# respirho2pile.net
KiCad netlist of a schematic drawn in EAGLE
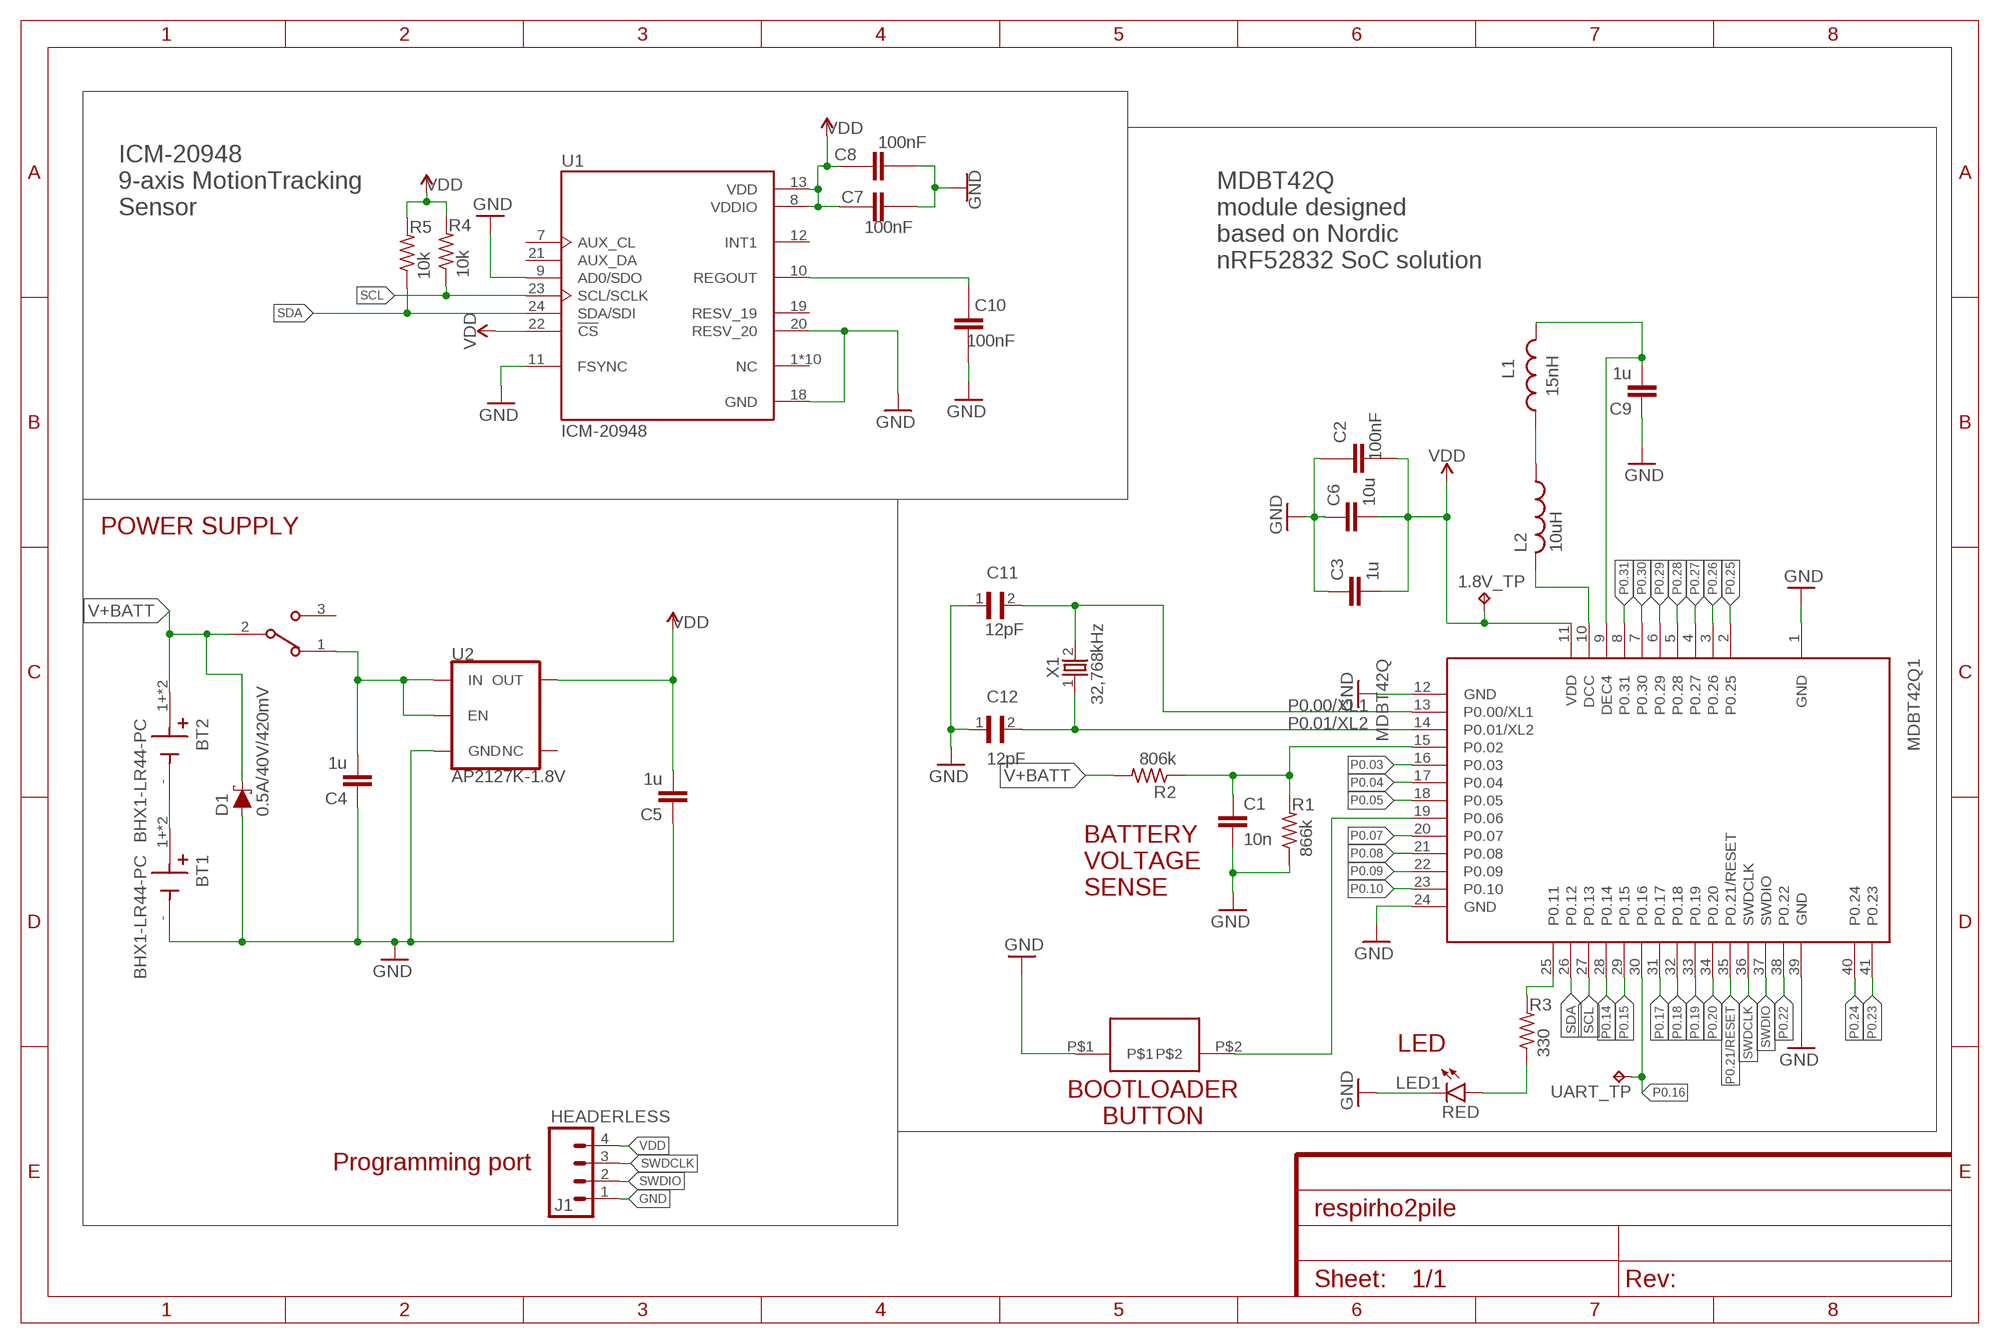
[diagram p0: schematic, sheet 1]

(export (version "E")
  (design (tool "Eeschema 10.0.6"))
  (components
    (comp (ref "1.8V_TP")
      (value "TPB1,27")
      (footprint "eagle-import:B1,27")
      (libsource (lib "eagle-import") (part "TPB1,27"))
    )
    (comp (ref "BT1")
      (value "BHX1-LR44-PC")
      (footprint "eagle-import:BAT_BHX1-LR44-PC")
      (fields (field (name "DIGI-KEY_PART_NUMBER") "BHX1-LR44-PC-G-ND") (field (name "MF") "MPD"))
      (libsource (lib "eagle-import") (part "BHX1-LR44-PC"))
    )
    (comp (ref "BT2")
      (value "BHX1-LR44-PC")
      (footprint "eagle-import:BAT_BHX1-LR44-PC")
      (fields (field (name "DIGI-KEY_PART_NUMBER") "BHX1-LR44-PC-G-ND") (field (name "MF") "MPD"))
      (libsource (lib "eagle-import") (part "BHX1-LR44-PC"))
    )
    (comp (ref "C1")
      (value "10n")
      (footprint "eagle-import:C0603")
      (libsource (lib "eagle-import") (part "C-EUC0603"))
    )
    (comp (ref "C2")
      (value "100nF")
      (footprint "eagle-import:CAPC1005X60")
      (fields
        (field (name "DIGI-KEY_PART_NUMBER") "311-1345-1-ND")
        (field (name "MF") "Yageo")
        (field (name "MP") "CC0402KRX7R6BB104")
      )
      (libsource (lib "eagle-import") (part "CC0402KRX7R6BB104"))
    )
    (comp (ref "C3")
      (value "1u")
      (footprint "eagle-import:C0603")
      (libsource (lib "eagle-import") (part "C-EUC0603"))
    )
    (comp (ref "C4")
      (value "1u")
      (footprint "eagle-import:C0603")
      (libsource (lib "eagle-import") (part "C-EUC0603"))
    )
    (comp (ref "C5")
      (value "1u")
      (footprint "eagle-import:C0603")
      (libsource (lib "eagle-import") (part "C-EUC0603"))
    )
    (comp (ref "C6")
      (value "10u")
      (footprint "eagle-import:C2012")
      (libsource (lib "eagle-import") (part "C-EUC2012"))
    )
    (comp (ref "C7")
      (value "100nF")
      (footprint "eagle-import:CAPC1005X60")
      (fields
        (field (name "DIGI-KEY_PART_NUMBER") "311-1345-1-ND")
        (field (name "MF") "Yageo")
        (field (name "MP") "CC0402KRX7R6BB104")
      )
      (libsource (lib "eagle-import") (part "CC0402KRX7R6BB104"))
    )
    (comp (ref "C8")
      (value "100nF")
      (footprint "eagle-import:CAPC1005X60")
      (fields
        (field (name "DIGI-KEY_PART_NUMBER") "311-1345-1-ND")
        (field (name "MF") "Yageo")
        (field (name "MP") "CC0402KRX7R6BB104")
      )
      (libsource (lib "eagle-import") (part "CC0402KRX7R6BB104"))
    )
    (comp (ref "C9")
      (value "1u")
      (footprint "eagle-import:C0603")
      (libsource (lib "eagle-import") (part "C-EUC0603"))
    )
    (comp (ref "C10")
      (value "100nF")
      (footprint "eagle-import:CAPC1005X60")
      (fields
        (field (name "DIGI-KEY_PART_NUMBER") "311-1345-1-ND")
        (field (name "MF") "Yageo")
        (field (name "MP") "CC0402KRX7R6BB104")
      )
      (libsource (lib "eagle-import") (part "CC0402KRX7R6BB104"))
    )
    (comp (ref "C11")
      (value "12pF")
      (footprint "eagle-import:CAPC1005X56N")
      (fields
        (field (name "DIGI-KEY_PART_NUMBER") "478-7871-1-ND")
        (field (name "MF") "AVX")
        (field (name "MP") "04025A120GAT2A")
      )
      (libsource (lib "eagle-import") (part "04025A120GAT2A"))
    )
    (comp (ref "C12")
      (value "12pF")
      (footprint "eagle-import:CAPC1005X56N")
      (fields
        (field (name "DIGI-KEY_PART_NUMBER") "478-7871-1-ND")
        (field (name "MF") "AVX")
        (field (name "MP") "04025A120GAT2A")
      )
      (libsource (lib "eagle-import") (part "04025A120GAT2A"))
    )
    (comp (ref "D1")
      (value "0.5A/40V/420mV")
      (footprint "eagle-import:SOD-323")
      (libsource (lib "eagle-import") (part "DIODE-SCHOTTKY-PMEG4005EJ"))
    )
    (comp (ref "J1")
      (value "HEADERLESS")
      (footprint "eagle-import:1X04")
      (libsource (lib "eagle-import") (part "CONN_04PTH"))
    )
    (comp (ref "L1")
      (value "15nH")
      (footprint "eagle-import:INDC1005X55N")
      (fields
        (field (name "DIGI-KEY_PART_NUMBER") "490-2625-1-ND")
        (field (name "MF") "Murata Electronics")
        (field (name "MP") "LQG15HS15NJ02D")
      )
      (libsource (lib "eagle-import") (part "LQG15HS15NJ02D"))
    )
    (comp (ref "L2")
      (value "10uH")
      (footprint "eagle-import:RESC0603_L")
      (libsource (lib "eagle-import") (part "INDUCTOR_0603_L"))
    )
    (comp (ref "LED1")
      (value "RED")
      (footprint "eagle-import:CHIPLED_1206")
      (libsource (lib "eagle-import") (part "LEDCHIPLED_1206"))
    )
    (comp (ref "MDBT42Q1")
      (value "MDBT42Q")
      (footprint "eagle-import:MDBT42Q")
      (libsource (lib "eagle-import") (part "MDBT42Q"))
    )
    (comp (ref "R1")
      (value "866k")
      (footprint "eagle-import:R0402")
      (libsource (lib "eagle-import") (part "R-US_R0402"))
    )
    (comp (ref "R2")
      (value "806k")
      (footprint "eagle-import:R0402")
      (libsource (lib "eagle-import") (part "R-US_R0402"))
    )
    (comp (ref "R3")
      (value "330")
      (footprint "eagle-import:R0402")
      (libsource (lib "eagle-import") (part "R-US_R0402"))
    )
    (comp (ref "R4")
      (value "10k")
      (footprint "eagle-import:R0402")
      (libsource (lib "eagle-import") (part "R-US_R0402"))
    )
    (comp (ref "R5")
      (value "10k")
      (footprint "eagle-import:R0402")
      (libsource (lib "eagle-import") (part "R-US_R0402"))
    )
    (comp (ref "SW1")
      (value "EG1213")
      (footprint "eagle-import:SW_EG1213")
      (fields (field (name "DIGI-KEY_PART_NUMBER") "EG1906-ND") (field (name "MF") "E-Switch"))
      (libsource (lib "eagle-import") (part "EG1213"))
    )
    (comp (ref "SW2")
      (value "KSS231GLFS")
      (footprint "eagle-import:KSS231GLFS")
      (libsource (lib "eagle-import") (part "KSS231GLFS"))
    )
    (comp (ref "U1")
      (value "ICM-20948")
      (footprint "eagle-import:QFN40P300X300X105-24N")
      (fields (field (name "MF") "TDK InvenSense"))
      (libsource (lib "eagle-import") (part "ICM-20948"))
    )
    (comp (ref "U2")
      (value "AP2127K-1.8V")
      (footprint "eagle-import:SOT23-5")
      (libsource (lib "eagle-import") (part "TPS7A0518PDBVTK-1.8V"))
    )
    (comp (ref "UART_TP")
      (value "TPB1,27")
      (footprint "eagle-import:B1,27")
      (libsource (lib "eagle-import") (part "TPB1,27"))
    )
    (comp (ref "X1")
      (value "32,768kHz")
      (footprint "eagle-import:XTAL_3215_N")
      (libsource (lib "eagle-import") (part "XTAL_32KHZ"))
    )
  )
  (nets
    (net (code "1") (name "/P0.00{slash}XL1") (class "Default")
      (node (ref "C11") (pin "2") (pinfunction "2_2") (pintype "passive"))
      (node (ref "MDBT42Q1") (pin "13") (pinfunction "P0.00/XL1_13") (pintype "bidirectional"))
      (node (ref "X1") (pin "2") (pinfunction "2_2") (pintype "passive"))
    )
    (net (code "2") (name "/P0.01{slash}XL2") (class "Default")
      (node (ref "C12") (pin "2") (pinfunction "2_2") (pintype "passive"))
      (node (ref "MDBT42Q1") (pin "14") (pinfunction "P0.01/XL2_14") (pintype "bidirectional"))
      (node (ref "X1") (pin "1") (pinfunction "1_1") (pintype "passive"))
    )
    (net (code "3") (name "GND") (class "Default")
      (node (ref "BT1") (pin "-") (pinfunction "-_-") (pintype "passive"))
      (node (ref "C1") (pin "2") (pinfunction "2_2") (pintype "passive"))
      (node (ref "C10") (pin "1") (pinfunction "1_1") (pintype "passive"))
      (node (ref "C11") (pin "1") (pinfunction "1_1") (pintype "passive"))
      (node (ref "C12") (pin "1") (pinfunction "1_1") (pintype "passive"))
      (node (ref "C2") (pin "2") (pinfunction "2_2") (pintype "passive"))
      (node (ref "C3") (pin "1") (pinfunction "1_1") (pintype "passive"))
      (node (ref "C4") (pin "1") (pinfunction "1_1") (pintype "passive"))
      (node (ref "C5") (pin "1") (pinfunction "1_1") (pintype "passive"))
      (node (ref "C6") (pin "1") (pinfunction "1_1") (pintype "passive"))
      (node (ref "C7") (pin "1") (pinfunction "1_1") (pintype "passive"))
      (node (ref "C8") (pin "1") (pinfunction "1_1") (pintype "passive"))
      (node (ref "C9") (pin "1") (pinfunction "1_1") (pintype "passive"))
      (node (ref "D1") (pin "A") (pinfunction "A_A") (pintype "passive"))
      (node (ref "J1") (pin "1") (pinfunction "1_1") (pintype "passive"))
      (node (ref "LED1") (pin "C") (pinfunction "C_C") (pintype "passive"))
      (node (ref "MDBT42Q1") (pin "1") (pinfunction "GND_1") (pintype "bidirectional"))
      (node (ref "MDBT42Q1") (pin "12") (pinfunction "GND_12") (pintype "bidirectional"))
      (node (ref "MDBT42Q1") (pin "24") (pinfunction "GND_24") (pintype "bidirectional"))
      (node (ref "MDBT42Q1") (pin "39") (pinfunction "GND_39") (pintype "bidirectional"))
      (node (ref "R1") (pin "1") (pinfunction "1_1") (pintype "passive"))
      (node (ref "SW2") (pin "P$1") (pinfunction "P$1_P$1") (pintype "bidirectional"))
      (node (ref "U1") (pin "11") (pinfunction "FSYNC_11") (pintype "input"))
      (node (ref "U1") (pin "18") (pinfunction "GND_18") (pintype "power_in"))
      (node (ref "U1") (pin "20") (pinfunction "RESV_20_20") (pintype "passive"))
      (node (ref "U1") (pin "9") (pinfunction "AD0/SDO_9") (pintype "bidirectional"))
      (node (ref "U2") (pin "2") (pinfunction "GND_2") (pintype "input"))
    )
    (net (code "4") (name "Net-(BT1-+-Pad1+)") (class "Default")
      (node (ref "BT1") (pin "1+") (pinfunction "+_1+") (pintype "passive"))
      (node (ref "BT1") (pin "2+") (pinfunction "+_2+") (pintype "passive"))
      (node (ref "BT2") (pin "-") (pinfunction "-_-") (pintype "passive"))
    )
    (net (code "5") (name "Net-(L1-Pad1)") (class "Default")
      (node (ref "L1") (pin "1") (pinfunction "1_1") (pintype "passive"))
      (node (ref "L2") (pin "1") (pinfunction "1_1") (pintype "passive"))
    )
    (net (code "6") (name "Net-(LED1-PadA)") (class "Default")
      (node (ref "LED1") (pin "A") (pinfunction "A_A") (pintype "passive"))
      (node (ref "R3") (pin "1") (pinfunction "1_1") (pintype "passive"))
    )
    (net (code "7") (name "Net-(MDBT42Q1-DCC)") (class "Default")
      (node (ref "L2") (pin "2") (pinfunction "2_2") (pintype "passive"))
      (node (ref "MDBT42Q1") (pin "10") (pinfunction "DCC_10") (pintype "bidirectional"))
    )
    (net (code "8") (name "Net-(MDBT42Q1-DEC4)") (class "Default")
      (node (ref "C9") (pin "2") (pinfunction "2_2") (pintype "passive"))
      (node (ref "L1") (pin "2") (pinfunction "2_2") (pintype "passive"))
      (node (ref "MDBT42Q1") (pin "9") (pinfunction "DEC4_9") (pintype "bidirectional"))
    )
    (net (code "9") (name "Net-(MDBT42Q1-P0.02)") (class "Default")
      (node (ref "C1") (pin "1") (pinfunction "1_1") (pintype "passive"))
      (node (ref "MDBT42Q1") (pin "15") (pinfunction "P0.02_15") (pintype "bidirectional"))
      (node (ref "R1") (pin "2") (pinfunction "2_2") (pintype "passive"))
      (node (ref "R2") (pin "1") (pinfunction "1_1") (pintype "passive"))
    )
    (net (code "10") (name "Net-(MDBT42Q1-P0.06)") (class "Default")
      (node (ref "MDBT42Q1") (pin "19") (pinfunction "P0.06_19") (pintype "bidirectional"))
      (node (ref "SW2") (pin "P$2") (pinfunction "P$2_P$2") (pintype "bidirectional"))
    )
    (net (code "11") (name "Net-(MDBT42Q1-P0.11)") (class "Default")
      (node (ref "MDBT42Q1") (pin "25") (pinfunction "P0.11_25") (pintype "bidirectional"))
      (node (ref "R3") (pin "2") (pinfunction "2_2") (pintype "passive"))
    )
    (net (code "12") (name "Net-(U1-REGOUT)") (class "Default")
      (node (ref "C10") (pin "2") (pinfunction "2_2") (pintype "passive"))
      (node (ref "U1") (pin "10") (pinfunction "REGOUT_10") (pintype "output"))
    )
    (net (code "13") (name "Net-(U2-EN)") (class "Default")
      (node (ref "C4") (pin "2") (pinfunction "2_2") (pintype "passive"))
      (node (ref "SW1") (pin "1") (pinfunction "1_1") (pintype "passive"))
      (node (ref "U2") (pin "1") (pinfunction "IN_1") (pintype "input"))
      (node (ref "U2") (pin "3") (pinfunction "EN_3") (pintype "input"))
    )
    (net (code "14") (name "P0.03") (class "Default")
      (node (ref "MDBT42Q1") (pin "16") (pinfunction "P0.03_16") (pintype "bidirectional"))
    )
    (net (code "15") (name "P0.04") (class "Default")
      (node (ref "MDBT42Q1") (pin "17") (pinfunction "P0.04_17") (pintype "bidirectional"))
    )
    (net (code "16") (name "P0.05") (class "Default")
      (node (ref "MDBT42Q1") (pin "18") (pinfunction "P0.05_18") (pintype "bidirectional"))
    )
    (net (code "17") (name "P0.07") (class "Default")
      (node (ref "MDBT42Q1") (pin "20") (pinfunction "P0.07_20") (pintype "bidirectional"))
    )
    (net (code "18") (name "P0.08") (class "Default")
      (node (ref "MDBT42Q1") (pin "21") (pinfunction "P0.08_21") (pintype "bidirectional"))
    )
    (net (code "19") (name "P0.09") (class "Default")
      (node (ref "MDBT42Q1") (pin "22") (pinfunction "P0.09_22") (pintype "bidirectional"))
    )
    (net (code "20") (name "P0.10") (class "Default")
      (node (ref "MDBT42Q1") (pin "23") (pinfunction "P0.10_23") (pintype "bidirectional"))
    )
    (net (code "21") (name "P0.14") (class "Default")
      (node (ref "MDBT42Q1") (pin "28") (pinfunction "P0.14_28") (pintype "bidirectional"))
    )
    (net (code "22") (name "P0.15") (class "Default")
      (node (ref "MDBT42Q1") (pin "29") (pinfunction "P0.15_29") (pintype "bidirectional"))
    )
    (net (code "23") (name "P0.16") (class "Default")
      (node (ref "MDBT42Q1") (pin "30") (pinfunction "P0.16_30") (pintype "bidirectional"))
      (node (ref "UART_TP") (pin "TP") (pinfunction "TP_TP") (pintype "input"))
    )
    (net (code "24") (name "P0.17") (class "Default")
      (node (ref "MDBT42Q1") (pin "31") (pinfunction "P0.17_31") (pintype "bidirectional"))
    )
    (net (code "25") (name "P0.18") (class "Default")
      (node (ref "MDBT42Q1") (pin "32") (pinfunction "P0.18_32") (pintype "bidirectional"))
    )
    (net (code "26") (name "P0.19") (class "Default")
      (node (ref "MDBT42Q1") (pin "33") (pinfunction "P0.19_33") (pintype "bidirectional"))
    )
    (net (code "27") (name "P0.20") (class "Default")
      (node (ref "MDBT42Q1") (pin "34") (pinfunction "P0.20_34") (pintype "bidirectional"))
    )
    (net (code "28") (name "P0.21{slash}RESET") (class "Default")
      (node (ref "MDBT42Q1") (pin "35") (pinfunction "P0.21/RESET_35") (pintype "bidirectional"))
    )
    (net (code "29") (name "P0.22") (class "Default")
      (node (ref "MDBT42Q1") (pin "38") (pinfunction "P0.22_38") (pintype "bidirectional"))
    )
    (net (code "30") (name "P0.23") (class "Default")
      (node (ref "MDBT42Q1") (pin "41") (pinfunction "P0.23_41") (pintype "bidirectional"))
    )
    (net (code "31") (name "P0.24") (class "Default")
      (node (ref "MDBT42Q1") (pin "40") (pinfunction "P0.24_40") (pintype "bidirectional"))
    )
    (net (code "32") (name "P0.25") (class "Default")
      (node (ref "MDBT42Q1") (pin "2") (pinfunction "P0.25_2") (pintype "bidirectional"))
    )
    (net (code "33") (name "P0.26") (class "Default")
      (node (ref "MDBT42Q1") (pin "3") (pinfunction "P0.26_3") (pintype "bidirectional"))
    )
    (net (code "34") (name "P0.27") (class "Default")
      (node (ref "MDBT42Q1") (pin "4") (pinfunction "P0.27_4") (pintype "bidirectional"))
    )
    (net (code "35") (name "P0.28") (class "Default")
      (node (ref "MDBT42Q1") (pin "5") (pinfunction "P0.28_5") (pintype "bidirectional"))
    )
    (net (code "36") (name "P0.29") (class "Default")
      (node (ref "MDBT42Q1") (pin "6") (pinfunction "P0.29_6") (pintype "bidirectional"))
    )
    (net (code "37") (name "P0.30") (class "Default")
      (node (ref "MDBT42Q1") (pin "7") (pinfunction "P0.30_7") (pintype "bidirectional"))
    )
    (net (code "38") (name "P0.31") (class "Default")
      (node (ref "MDBT42Q1") (pin "8") (pinfunction "P0.31_8") (pintype "bidirectional"))
    )
    (net (code "39") (name "SCL") (class "Default")
      (node (ref "MDBT42Q1") (pin "27") (pinfunction "P0.13_27") (pintype "bidirectional"))
      (node (ref "R4") (pin "1") (pinfunction "1_1") (pintype "passive"))
      (node (ref "U1") (pin "23") (pinfunction "SCL/SCLK_23") (pintype "input"))
    )
    (net (code "40") (name "SDA") (class "Default")
      (node (ref "MDBT42Q1") (pin "26") (pinfunction "P0.12_26") (pintype "bidirectional"))
      (node (ref "R5") (pin "1") (pinfunction "1_1") (pintype "passive"))
      (node (ref "U1") (pin "24") (pinfunction "SDA/SDI_24") (pintype "bidirectional"))
    )
    (net (code "41") (name "SWDCLK") (class "Default")
      (node (ref "J1") (pin "3") (pinfunction "3_3") (pintype "passive"))
      (node (ref "MDBT42Q1") (pin "36") (pinfunction "SWDCLK_36") (pintype "bidirectional"))
    )
    (net (code "42") (name "SWDIO") (class "Default")
      (node (ref "J1") (pin "2") (pinfunction "2_2") (pintype "passive"))
      (node (ref "MDBT42Q1") (pin "37") (pinfunction "SWDIO_37") (pintype "bidirectional"))
    )
    (net (code "43") (name "V+BATT") (class "Default")
      (node (ref "BT2") (pin "1+") (pinfunction "+_1+") (pintype "passive"))
      (node (ref "BT2") (pin "2+") (pinfunction "+_2+") (pintype "passive"))
      (node (ref "D1") (pin "C") (pinfunction "C_C") (pintype "passive"))
      (node (ref "R2") (pin "2") (pinfunction "2_2") (pintype "passive"))
      (node (ref "SW1") (pin "2") (pinfunction "2_2") (pintype "passive"))
    )
    (net (code "44") (name "VDD") (class "Default")
      (node (ref "1.8V_TP") (pin "TP") (pinfunction "TP_TP") (pintype "input"))
      (node (ref "C2") (pin "1") (pinfunction "1_1") (pintype "passive"))
      (node (ref "C3") (pin "2") (pinfunction "2_2") (pintype "passive"))
      (node (ref "C5") (pin "2") (pinfunction "2_2") (pintype "passive"))
      (node (ref "C6") (pin "2") (pinfunction "2_2") (pintype "passive"))
      (node (ref "C7") (pin "2") (pinfunction "2_2") (pintype "passive"))
      (node (ref "C8") (pin "2") (pinfunction "2_2") (pintype "passive"))
      (node (ref "J1") (pin "4") (pinfunction "4_4") (pintype "passive"))
      (node (ref "MDBT42Q1") (pin "11") (pinfunction "VDD_11") (pintype "bidirectional"))
      (node (ref "R4") (pin "2") (pinfunction "2_2") (pintype "passive"))
      (node (ref "R5") (pin "2") (pinfunction "2_2") (pintype "passive"))
      (node (ref "U1") (pin "13") (pinfunction "VDD_13") (pintype "power_in"))
      (node (ref "U1") (pin "22") (pinfunction "~{CS}_22") (pintype "input"))
      (node (ref "U1") (pin "8") (pinfunction "VDDIO_8") (pintype "power_in"))
      (node (ref "U2") (pin "5") (pinfunction "OUT_5") (pintype "passive"))
    )
    (net (code "45") (name "unconnected-(SW1-Pad3)") (class "Default")
      (node (ref "SW1") (pin "3") (pinfunction "3_3") (pintype "passive"))
    )
    (net (code "46") (name "unconnected-(U1-AUX_CL-Pad7)") (class "Default")
      (node (ref "U1") (pin "7") (pinfunction "AUX_CL_7") (pintype "input"))
    )
    (net (code "47") (name "unconnected-(U1-AUX_DA-Pad21)") (class "Default")
      (node (ref "U1") (pin "21") (pinfunction "AUX_DA_21") (pintype "bidirectional"))
    )
    (net (code "48") (name "unconnected-(U1-INT1-Pad12)") (class "Default")
      (node (ref "U1") (pin "12") (pinfunction "INT1_12") (pintype "output"))
    )
    (net (code "49") (name "unconnected-(U1-NC-Pad1)") (class "Default")
      (node (ref "U1") (pin "1") (pinfunction "NC_1") (pintype "no_connect"))
    )
    (net (code "50") (name "unconnected-(U1-NC-Pad2)") (class "Default")
      (node (ref "U1") (pin "2") (pinfunction "NC_2") (pintype "no_connect"))
    )
    (net (code "51") (name "unconnected-(U1-NC-Pad3)") (class "Default")
      (node (ref "U1") (pin "3") (pinfunction "NC_3") (pintype "no_connect"))
    )
    (net (code "52") (name "unconnected-(U1-NC-Pad4)") (class "Default")
      (node (ref "U1") (pin "4") (pinfunction "NC_4") (pintype "no_connect"))
    )
    (net (code "53") (name "unconnected-(U1-NC-Pad5)") (class "Default")
      (node (ref "U1") (pin "5") (pinfunction "NC_5") (pintype "no_connect"))
    )
    (net (code "54") (name "unconnected-(U1-NC-Pad6)") (class "Default")
      (node (ref "U1") (pin "6") (pinfunction "NC_6") (pintype "no_connect"))
    )
    (net (code "55") (name "unconnected-(U1-NC-Pad14)") (class "Default")
      (node (ref "U1") (pin "14") (pinfunction "NC_14") (pintype "no_connect"))
    )
    (net (code "56") (name "unconnected-(U1-NC-Pad15)") (class "Default")
      (node (ref "U1") (pin "15") (pinfunction "NC_15") (pintype "no_connect"))
    )
    (net (code "57") (name "unconnected-(U1-NC-Pad16)") (class "Default")
      (node (ref "U1") (pin "16") (pinfunction "NC_16") (pintype "no_connect"))
    )
    (net (code "58") (name "unconnected-(U1-NC-Pad17)") (class "Default")
      (node (ref "U1") (pin "17") (pinfunction "NC_17") (pintype "no_connect"))
    )
    (net (code "59") (name "unconnected-(U1-RESV_19-Pad19)") (class "Default")
      (node (ref "U1") (pin "19") (pinfunction "RESV_19_19") (pintype "passive"))
    )
    (net (code "60") (name "unconnected-(U2-NC-Pad4)") (class "Default")
      (node (ref "U2") (pin "4") (pinfunction "NC_4") (pintype "no_connect"))
    )
  )
)
